# DoubleLna.net
KiCad netlist of a schematic drawn in EAGLE
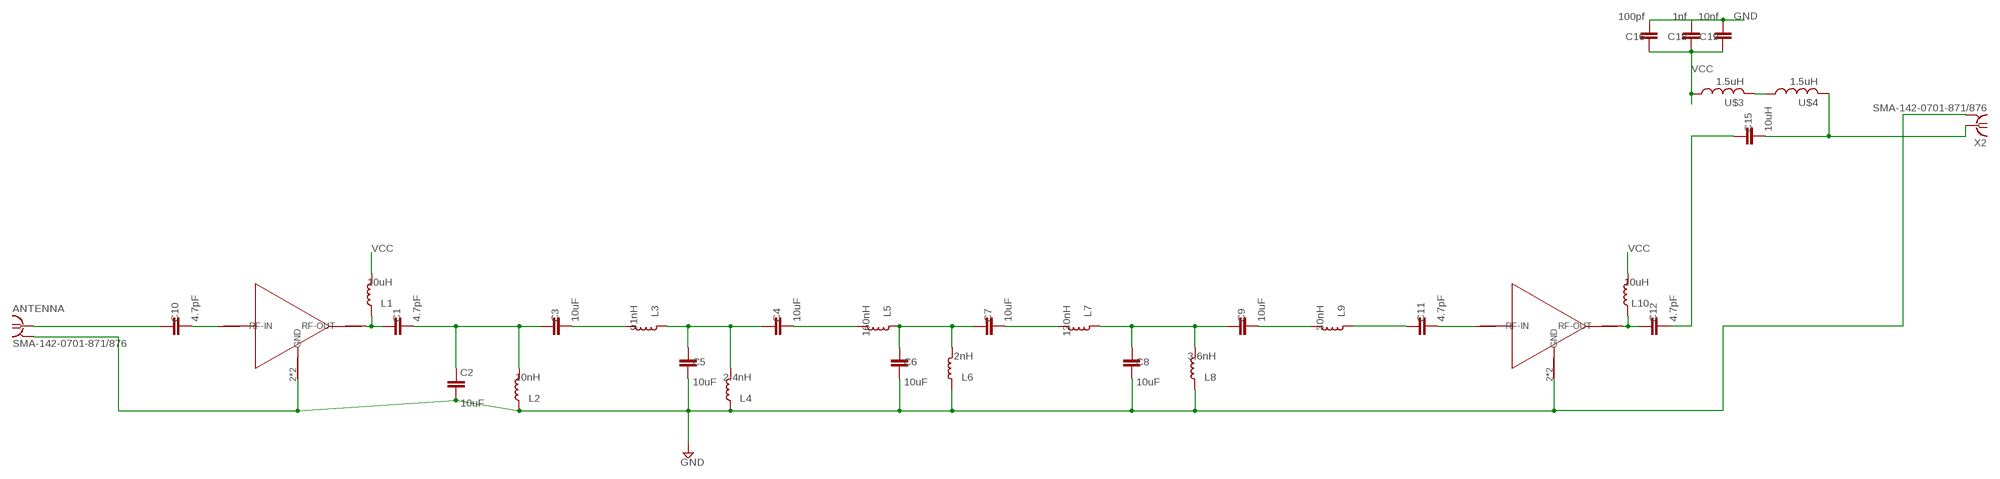
[diagram p0: schematic, sheet 1]

(export (version "E")
  (design (tool "Eeschema 10.0.6"))
  (components
    (comp (ref "ANTENNA")
      (value "SMA-142-0701-871/876")
      (footprint "eagle-import:J502-ND-142-0701-871_876")
      (fields (field (name "MF") "JOHNSON COMPONENTS") (field (name "MPN") "142-0701-871"))
      (libsource (lib "eagle-import") (part "SMA-142-0701-871/876"))
    )
    (comp (ref "C1")
      (value "4.7pF")
      (footprint "eagle-import:0603")
      (libsource (lib "eagle-import") (part "10UF-0603-6.3V-20%"))
    )
    (comp (ref "C2")
      (value "10uF")
      (footprint "eagle-import:0603")
      (libsource (lib "eagle-import") (part "10UF-0603-6.3V-20%"))
    )
    (comp (ref "C3")
      (value "10uF")
      (footprint "eagle-import:0603")
      (libsource (lib "eagle-import") (part "10UF-0603-6.3V-20%"))
    )
    (comp (ref "C4")
      (value "10uF")
      (footprint "eagle-import:0603")
      (libsource (lib "eagle-import") (part "10UF-0603-6.3V-20%"))
    )
    (comp (ref "C5")
      (value "10uF")
      (footprint "eagle-import:0603")
      (libsource (lib "eagle-import") (part "10UF-0603-6.3V-20%"))
    )
    (comp (ref "C6")
      (value "10uF")
      (footprint "eagle-import:0603")
      (libsource (lib "eagle-import") (part "10UF-0603-6.3V-20%"))
    )
    (comp (ref "C7")
      (value "10uF")
      (footprint "eagle-import:0603")
      (libsource (lib "eagle-import") (part "10UF-0603-6.3V-20%"))
    )
    (comp (ref "C8")
      (value "10uF")
      (footprint "eagle-import:0603")
      (libsource (lib "eagle-import") (part "10UF-0603-6.3V-20%"))
    )
    (comp (ref "C9")
      (value "10uF")
      (footprint "eagle-import:0603")
      (libsource (lib "eagle-import") (part "10UF-0603-6.3V-20%"))
    )
    (comp (ref "C10")
      (value "4.7pF")
      (footprint "eagle-import:0603")
      (libsource (lib "eagle-import") (part "10UF-0603-6.3V-20%"))
    )
    (comp (ref "C11")
      (value "4.7pF")
      (footprint "eagle-import:0603")
      (libsource (lib "eagle-import") (part "10UF-0603-6.3V-20%"))
    )
    (comp (ref "C12")
      (value "4.7pF")
      (footprint "eagle-import:0603")
      (libsource (lib "eagle-import") (part "10UF-0603-6.3V-20%"))
    )
    (comp (ref "C15")
      (value "10uH")
      (footprint "eagle-import:0603")
      (libsource (lib "eagle-import") (part "10UF-0603-6.3V-20%"))
    )
    (comp (ref "C16")
      (value "100pf")
      (footprint "eagle-import:0603")
      (libsource (lib "eagle-import") (part "10UF-0603-6.3V-20%"))
    )
    (comp (ref "C18")
      (value "1nf")
      (footprint "eagle-import:0603")
      (libsource (lib "eagle-import") (part "10UF-0603-6.3V-20%"))
    )
    (comp (ref "C19")
      (value "10nf")
      (footprint "eagle-import:0603")
      (libsource (lib "eagle-import") (part "10UF-0603-6.3V-20%"))
    )
    (comp (ref "L1")
      (value "10uH")
      (footprint "eagle-import:L0603")
      (libsource (lib "eagle-import") (part "L_0603"))
    )
    (comp (ref "L2")
      (value "10nH")
      (footprint "eagle-import:L0603")
      (libsource (lib "eagle-import") (part "L_0603"))
    )
    (comp (ref "L3")
      (value "91nH")
      (footprint "eagle-import:L0603")
      (libsource (lib "eagle-import") (part "L_0603"))
    )
    (comp (ref "L4")
      (value "2.4nH")
      (footprint "eagle-import:L0603")
      (libsource (lib "eagle-import") (part "L_0603"))
    )
    (comp (ref "L5")
      (value "160nH")
      (footprint "eagle-import:L0603")
      (libsource (lib "eagle-import") (part "L_0603"))
    )
    (comp (ref "L6")
      (value "2nH")
      (footprint "eagle-import:L0603")
      (libsource (lib "eagle-import") (part "L_0603"))
    )
    (comp (ref "L7")
      (value "130nH")
      (footprint "eagle-import:L0603")
      (libsource (lib "eagle-import") (part "L_0603"))
    )
    (comp (ref "L8")
      (value "3.6nH")
      (footprint "eagle-import:L0603")
      (libsource (lib "eagle-import") (part "L_0603"))
    )
    (comp (ref "L9")
      (value "30nH")
      (footprint "eagle-import:L0603")
      (libsource (lib "eagle-import") (part "L_0603"))
    )
    (comp (ref "L10")
      (value "10uH")
      (footprint "eagle-import:L0603")
      (libsource (lib "eagle-import") (part "L_0603"))
    )
    (comp (ref "U$1")
      (value "PSA4-5043+")
      (footprint "eagle-import:PSA4-5043+")
      (fields (field (name "MF") "Mini-Circuits"))
      (libsource (lib "eagle-import") (part "PSA4-5043+"))
    )
    (comp (ref "U$2")
      (value "PSA4-5043+")
      (footprint "eagle-import:PSA4-5043+")
      (fields (field (name "MF") "Mini-Circuits"))
      (libsource (lib "eagle-import") (part "PSA4-5043+"))
    )
    (comp (ref "U$3")
      (value "1.5uH")
      (footprint "eagle-import:C0504")
      (libsource (lib "eagle-import") (part "L504"))
    )
    (comp (ref "U$4")
      (value "1.5uH")
      (footprint "eagle-import:C0504")
      (libsource (lib "eagle-import") (part "L504"))
    )
    (comp (ref "X2")
      (value "SMA-142-0701-871/876")
      (footprint "eagle-import:J502-ND-142-0701-871_876")
      (fields (field (name "MF") "JOHNSON COMPONENTS") (field (name "MPN") "142-0701-871"))
      (libsource (lib "eagle-import") (part "SMA-142-0701-871/876"))
    )
  )
  (nets
    (net (code "1") (name "/VCC") (class "Default")
      (node (ref "C16") (pin "1") (pinfunction "1_1") (pintype "passive"))
      (node (ref "C18") (pin "1") (pinfunction "1_1") (pintype "passive"))
      (node (ref "C19") (pin "1") (pinfunction "1_1") (pintype "passive"))
      (node (ref "L1") (pin "1") (pinfunction "1_1") (pintype "passive"))
      (node (ref "L10") (pin "1") (pinfunction "1_1") (pintype "passive"))
      (node (ref "U$3") (pin "1") (pinfunction "1_1") (pintype "passive"))
    )
    (net (code "2") (name "GND") (class "Default")
      (node (ref "ANTENNA") (pin "G@1") (pinfunction "2_G@1") (pintype "passive"))
      (node (ref "ANTENNA") (pin "G@2") (pinfunction "2_G@2") (pintype "passive"))
      (node (ref "ANTENNA") (pin "G@3") (pinfunction "2_G@3") (pintype "passive"))
      (node (ref "ANTENNA") (pin "G@4") (pinfunction "2_G@4") (pintype "passive"))
      (node (ref "C16") (pin "2") (pinfunction "2_2") (pintype "passive"))
      (node (ref "C18") (pin "2") (pinfunction "2_2") (pintype "passive"))
      (node (ref "C19") (pin "2") (pinfunction "2_2") (pintype "passive"))
      (node (ref "C2") (pin "2") (pinfunction "2_2") (pintype "passive"))
      (node (ref "C5") (pin "2") (pinfunction "2_2") (pintype "passive"))
      (node (ref "C6") (pin "2") (pinfunction "2_2") (pintype "passive"))
      (node (ref "C8") (pin "2") (pinfunction "2_2") (pintype "passive"))
      (node (ref "L2") (pin "2") (pinfunction "2_2") (pintype "passive"))
      (node (ref "L4") (pin "2") (pinfunction "2_2") (pintype "passive"))
      (node (ref "L6") (pin "2") (pinfunction "2_2") (pintype "passive"))
      (node (ref "L8") (pin "2") (pinfunction "2_2") (pintype "passive"))
      (node (ref "U$1") (pin "2") (pinfunction "GND_2") (pintype "bidirectional"))
      (node (ref "U$1") (pin "4") (pinfunction "GND_4") (pintype "bidirectional"))
      (node (ref "U$2") (pin "2") (pinfunction "GND_2") (pintype "bidirectional"))
      (node (ref "U$2") (pin "4") (pinfunction "GND_4") (pintype "bidirectional"))
      (node (ref "X2") (pin "G@1") (pinfunction "2_G@1") (pintype "passive"))
      (node (ref "X2") (pin "G@2") (pinfunction "2_G@2") (pintype "passive"))
      (node (ref "X2") (pin "G@3") (pinfunction "2_G@3") (pintype "passive"))
      (node (ref "X2") (pin "G@4") (pinfunction "2_G@4") (pintype "passive"))
    )
    (net (code "3") (name "Net-(ANTENNA-Pad1)") (class "Default")
      (node (ref "ANTENNA") (pin "1") (pinfunction "1_1") (pintype "passive"))
      (node (ref "C10") (pin "1") (pinfunction "1_1") (pintype "passive"))
    )
    (net (code "4") (name "Net-(C1-Pad2)") (class "Default")
      (node (ref "C1") (pin "2") (pinfunction "2_2") (pintype "passive"))
      (node (ref "C2") (pin "1") (pinfunction "1_1") (pintype "passive"))
      (node (ref "C3") (pin "1") (pinfunction "1_1") (pintype "passive"))
      (node (ref "L2") (pin "1") (pinfunction "1_1") (pintype "passive"))
    )
    (net (code "5") (name "Net-(C3-Pad2)") (class "Default")
      (node (ref "C3") (pin "2") (pinfunction "2_2") (pintype "passive"))
      (node (ref "L3") (pin "1") (pinfunction "1_1") (pintype "passive"))
    )
    (net (code "6") (name "Net-(C4-Pad1)") (class "Default")
      (node (ref "C4") (pin "1") (pinfunction "1_1") (pintype "passive"))
      (node (ref "C5") (pin "1") (pinfunction "1_1") (pintype "passive"))
      (node (ref "L3") (pin "2") (pinfunction "2_2") (pintype "passive"))
      (node (ref "L4") (pin "1") (pinfunction "1_1") (pintype "passive"))
    )
    (net (code "7") (name "Net-(C4-Pad2)") (class "Default")
      (node (ref "C4") (pin "2") (pinfunction "2_2") (pintype "passive"))
      (node (ref "L5") (pin "1") (pinfunction "1_1") (pintype "passive"))
    )
    (net (code "8") (name "Net-(C6-Pad1)") (class "Default")
      (node (ref "C6") (pin "1") (pinfunction "1_1") (pintype "passive"))
      (node (ref "C7") (pin "1") (pinfunction "1_1") (pintype "passive"))
      (node (ref "L5") (pin "2") (pinfunction "2_2") (pintype "passive"))
      (node (ref "L6") (pin "1") (pinfunction "1_1") (pintype "passive"))
    )
    (net (code "9") (name "Net-(C7-Pad2)") (class "Default")
      (node (ref "C7") (pin "2") (pinfunction "2_2") (pintype "passive"))
      (node (ref "L7") (pin "1") (pinfunction "1_1") (pintype "passive"))
    )
    (net (code "10") (name "Net-(C8-Pad1)") (class "Default")
      (node (ref "C8") (pin "1") (pinfunction "1_1") (pintype "passive"))
      (node (ref "C9") (pin "1") (pinfunction "1_1") (pintype "passive"))
      (node (ref "L7") (pin "2") (pinfunction "2_2") (pintype "passive"))
      (node (ref "L8") (pin "1") (pinfunction "1_1") (pintype "passive"))
    )
    (net (code "11") (name "Net-(C9-Pad2)") (class "Default")
      (node (ref "C9") (pin "2") (pinfunction "2_2") (pintype "passive"))
      (node (ref "L9") (pin "1") (pinfunction "1_1") (pintype "passive"))
    )
    (net (code "12") (name "Net-(C11-Pad1)") (class "Default")
      (node (ref "C11") (pin "1") (pinfunction "1_1") (pintype "passive"))
      (node (ref "L9") (pin "2") (pinfunction "2_2") (pintype "passive"))
    )
    (net (code "13") (name "Net-(C12-Pad2)") (class "Default")
      (node (ref "C12") (pin "2") (pinfunction "2_2") (pintype "passive"))
      (node (ref "C15") (pin "1") (pinfunction "1_1") (pintype "passive"))
    )
    (net (code "14") (name "Net-(C15-Pad2)") (class "Default")
      (node (ref "C15") (pin "2") (pinfunction "2_2") (pintype "passive"))
      (node (ref "U$4") (pin "2") (pinfunction "2_2") (pintype "passive"))
      (node (ref "X2") (pin "1") (pinfunction "1_1") (pintype "passive"))
    )
    (net (code "15") (name "Net-(U$1-RF-IN)") (class "Default")
      (node (ref "C10") (pin "2") (pinfunction "2_2") (pintype "passive"))
      (node (ref "U$1") (pin "3") (pinfunction "RF-IN_3") (pintype "bidirectional"))
    )
    (net (code "16") (name "Net-(U$1-RF-OUT)") (class "Default")
      (node (ref "C1") (pin "1") (pinfunction "1_1") (pintype "passive"))
      (node (ref "L1") (pin "2") (pinfunction "2_2") (pintype "passive"))
      (node (ref "U$1") (pin "1") (pinfunction "RF-OUT_1") (pintype "bidirectional"))
    )
    (net (code "17") (name "Net-(U$2-RF-IN)") (class "Default")
      (node (ref "C11") (pin "2") (pinfunction "2_2") (pintype "passive"))
      (node (ref "U$2") (pin "3") (pinfunction "RF-IN_3") (pintype "bidirectional"))
    )
    (net (code "18") (name "Net-(U$2-RF-OUT)") (class "Default")
      (node (ref "C12") (pin "1") (pinfunction "1_1") (pintype "passive"))
      (node (ref "L10") (pin "2") (pinfunction "2_2") (pintype "passive"))
      (node (ref "U$2") (pin "1") (pinfunction "RF-OUT_1") (pintype "bidirectional"))
    )
    (net (code "19") (name "Net-(U$3-Pad2)") (class "Default")
      (node (ref "U$3") (pin "2") (pinfunction "2_2") (pintype "passive"))
      (node (ref "U$4") (pin "1") (pinfunction "1_1") (pintype "passive"))
    )
  )
)
